# ESP8266.net
KiCad netlist of a schematic drawn in Altium Designer
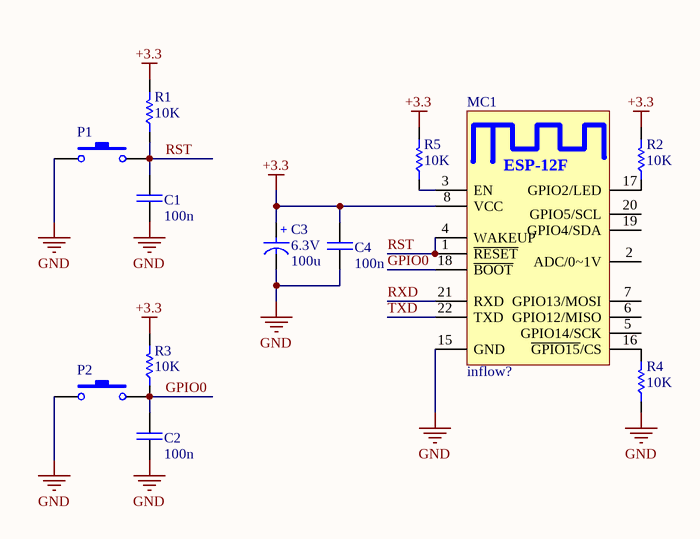
[diagram p0: ESP8266.SchDoc]

(export (version "E")
  (design (tool "Eeschema 10.0.6"))
  (components
    (comp (ref "C1")
      (value "100n")
      (footprint "CAP 0805/2012")
      (description "Bipolar ceramic capacitor SMD")
      (fields (field (name "VALIDATION") "Valid"))
      (libsource (lib "aKaReZa") (part "Cap_Multi_SMD_100nF_0805"))
    )
    (comp (ref "C2")
      (value "100n")
      (footprint "CAP 0805/2012")
      (description "Bipolar ceramic capacitor SMD")
      (fields (field (name "VALIDATION") "Valid"))
      (libsource (lib "aKaReZa") (part "Cap_Multi_SMD_100nF_0805"))
    )
    (comp (ref "C3")
      (value "100u")
      (footprint "cap 03")
      (description "Electrolit Capacitor")
      (fields (field (name "RATING") "6.3V") (field (name "VALIDATION") "Valid"))
      (libsource (lib "aKaReZa") (part "Cap_Electrolit"))
    )
    (comp (ref "C4")
      (value "100n")
      (footprint "CAP 0805/2012")
      (description "Bipolar ceramic capacitor SMD")
      (fields (field (name "VALIDATION") "Valid"))
      (libsource (lib "aKaReZa") (part "Cap_Multi_SMD_100nF_0805"))
    )
    (comp (ref "MC1")
      (value "ESP8266-12F")
      (footprint "ESP8266_12F")
      (description "ESP8266 WIFI Module Model ESP-12F")
      (fields (field (name "INFLOW") "inflow?") (field (name "VALIDATION") "NT"))
      (libsource (lib "aKaReZa") (part "ModSen_Com_ESP-12F"))
    )
    (comp (ref "P1")
      (value "Value?")
      (footprint "JST XH B2B-XH-A")
      (description "PushBottom Connector 2'Pin")
      (fields (field (name "VALIDATION") "Valid"))
      (libsource (lib "aKaReZa") (part "Con_PushButtom"))
    )
    (comp (ref "P2")
      (value "Value?")
      (footprint "JST XH B2B-XH-A")
      (description "PushBottom Connector 2'Pin")
      (fields (field (name "VALIDATION") "Valid"))
      (libsource (lib "aKaReZa") (part "Con_PushButtom"))
    )
    (comp (ref "R1")
      (value "10K")
      (footprint "RES 0805 (2012X06L)")
      (description "Resistor")
      (fields (field (name "VALIDATION") "Valid"))
      (libsource (lib "aKaReZa") (part "Res_SMD_0805"))
    )
    (comp (ref "R2")
      (value "10K")
      (footprint "RES 0805 (2012X06L)")
      (description "Resistor")
      (fields (field (name "VALIDATION") "Valid"))
      (libsource (lib "aKaReZa") (part "Res_SMD_0805"))
    )
    (comp (ref "R3")
      (value "10K")
      (footprint "RES 0805 (2012X06L)")
      (description "Resistor")
      (fields (field (name "VALIDATION") "Valid"))
      (libsource (lib "aKaReZa") (part "Res_SMD_0805"))
    )
    (comp (ref "R4")
      (value "10K")
      (footprint "RES 0805 (2012X06L)")
      (description "Resistor")
      (fields (field (name "VALIDATION") "Valid"))
      (libsource (lib "aKaReZa") (part "Res_SMD_0805"))
    )
    (comp (ref "R5")
      (value "10K")
      (footprint "RES 0805 (2012X06L)")
      (description "Resistor")
      (fields (field (name "VALIDATION") "Valid"))
      (libsource (lib "aKaReZa") (part "Res_SMD_0805"))
    )
  )
  (nets
    (net (code "1") (name "+3.3") (class "Default")
      (node (ref "C3") (pin "1") (pinfunction "+_1") (pintype "passive"))
      (node (ref "C4") (pin "1") (pinfunction "1_1") (pintype "passive"))
      (node (ref "MC1") (pin "8") (pinfunction "VCC_8") (pintype "power_in"))
      (node (ref "R1") (pin "2") (pinfunction "2_2") (pintype "passive"))
      (node (ref "R2") (pin "2") (pinfunction "2_2") (pintype "passive"))
      (node (ref "R3") (pin "2") (pinfunction "2_2") (pintype "passive"))
      (node (ref "R5") (pin "2") (pinfunction "2_2") (pintype "passive"))
    )
    (net (code "2") (name "/GPIO0") (class "Default")
      (node (ref "C2") (pin "1") (pinfunction "1_1") (pintype "passive"))
      (node (ref "MC1") (pin "18") (pinfunction "~{BOOT}_18") (pintype "passive"))
      (node (ref "P2") (pin "2") (pinfunction "2_2") (pintype "passive"))
      (node (ref "R3") (pin "1") (pinfunction "1_1") (pintype "passive"))
    )
    (net (code "3") (name "/RST") (class "Default")
      (node (ref "C1") (pin "1") (pinfunction "1_1") (pintype "passive"))
      (node (ref "MC1") (pin "1") (pinfunction "~{RESET}_1") (pintype "passive"))
      (node (ref "MC1") (pin "4") (pinfunction "WAKEUP_4") (pintype "passive"))
      (node (ref "P1") (pin "2") (pinfunction "2_2") (pintype "passive"))
      (node (ref "R1") (pin "1") (pinfunction "1_1") (pintype "passive"))
    )
    (net (code "4") (name "/RXD") (class "Default")
      (node (ref "MC1") (pin "21") (pinfunction "RXD_21") (pintype "passive"))
    )
    (net (code "5") (name "/TXD") (class "Default")
      (node (ref "MC1") (pin "22") (pinfunction "TXD_22") (pintype "passive"))
    )
    (net (code "6") (name "GND") (class "Default")
      (node (ref "C1") (pin "2") (pinfunction "2_2") (pintype "passive"))
      (node (ref "C2") (pin "2") (pinfunction "2_2") (pintype "passive"))
      (node (ref "C3") (pin "2") (pinfunction "-_2") (pintype "passive"))
      (node (ref "C4") (pin "2") (pinfunction "2_2") (pintype "passive"))
      (node (ref "MC1") (pin "15") (pinfunction "GND_15") (pintype "power_in"))
      (node (ref "P1") (pin "1") (pinfunction "1_1") (pintype "passive"))
      (node (ref "P2") (pin "1") (pinfunction "1_1") (pintype "passive"))
      (node (ref "R4") (pin "1") (pinfunction "1_1") (pintype "passive"))
    )
    (net (code "7") (name "Net-(MC1-EN)") (class "Default")
      (node (ref "MC1") (pin "3") (pinfunction "EN_3") (pintype "passive"))
      (node (ref "R5") (pin "1") (pinfunction "1_1") (pintype "passive"))
    )
    (net (code "8") (name "Net-(MC1-GPIO2{slash}LED)") (class "Default")
      (node (ref "MC1") (pin "17") (pinfunction "GPIO2/LED_17") (pintype "passive"))
      (node (ref "R2") (pin "1") (pinfunction "1_1") (pintype "passive"))
    )
    (net (code "9") (name "Net-(MC1-~{GPIO15}{slash}CS)") (class "Default")
      (node (ref "MC1") (pin "16") (pinfunction "~{GPIO15}/CS_16") (pintype "passive"))
      (node (ref "R4") (pin "2") (pinfunction "2_2") (pintype "passive"))
    )
    (net (code "10") (name "unconnected-(MC1-ADC{slash}0~1V-Pad2)") (class "Default")
      (node (ref "MC1") (pin "2") (pinfunction "ADC/0~1V_2") (pintype "passive"))
    )
    (net (code "11") (name "unconnected-(MC1-GPIO4{slash}SDA-Pad19)") (class "Default")
      (node (ref "MC1") (pin "19") (pinfunction "GPIO4/SDA_19") (pintype "passive"))
    )
    (net (code "12") (name "unconnected-(MC1-GPIO5{slash}SCL-Pad20)") (class "Default")
      (node (ref "MC1") (pin "20") (pinfunction "GPIO5/SCL_20") (pintype "passive"))
    )
    (net (code "13") (name "unconnected-(MC1-GPIO12{slash}MISO-Pad6)") (class "Default")
      (node (ref "MC1") (pin "6") (pinfunction "GPIO12/MISO_6") (pintype "passive"))
    )
    (net (code "14") (name "unconnected-(MC1-GPIO13{slash}MOSI-Pad7)") (class "Default")
      (node (ref "MC1") (pin "7") (pinfunction "GPIO13/MOSI_7") (pintype "passive"))
    )
    (net (code "15") (name "unconnected-(MC1-GPIO14{slash}SCK-Pad5)") (class "Default")
      (node (ref "MC1") (pin "5") (pinfunction "GPIO14/SCK_5") (pintype "passive"))
    )
  )
)
